# SI1125HD_replacement.net
KiCad netlist of a schematic drawn in Altium Designer
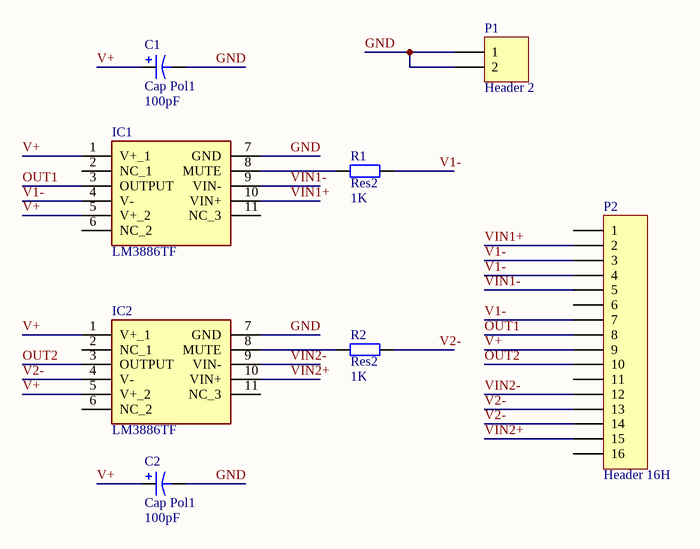
[diagram p0: SI1125HD_replacement.SchDoc]

(export (version "E")
  (design (tool "Eeschema 10.0.6"))
  (components
    (comp (ref "C1")
      (value "Cap Pol1")
      (footprint "RB5-10.5")
      (description "Polarized Capacitor (Radial)")
      (fields (field (name "ALTIUM_VALUE") "100pF") (field (name "PUBLISHER") "Altium Limited"))
      (libsource (lib "Miscellaneous Devices") (part "Cap Pol1"))
    )
    (comp (ref "C2")
      (value "Cap Pol1")
      (footprint "RB5-10.5")
      (description "Polarized Capacitor (Radial)")
      (fields (field (name "ALTIUM_VALUE") "100pF") (field (name "PUBLISHER") "Altium Limited"))
      (libsource (lib "Miscellaneous Devices") (part "Cap Pol1"))
    )
    (comp (ref "IC1")
      (value "LM3886TF")
      (footprint "SamacSys:TO158P462X2002X2328-11P")
      (description "Integrated Circuit")
      (fields (field (name "MOUSER PART NUMBER") "926-LM3886TF"))
      (libsource (lib "*") (part "LM3886TF"))
    )
    (comp (ref "IC2")
      (value "LM3886TF")
      (footprint "SamacSys:TO158P462X2002X2328-11P")
      (description "Integrated Circuit")
      (fields (field (name "MOUSER PART NUMBER") "926-LM3886TF"))
      (libsource (lib "*") (part "LM3886TF"))
    )
    (comp (ref "P1")
      (value "Header 2")
      (footprint "HDR1X2")
      (description "Header, 2-Pin")
      (fields (field (name "PUBLISHER") "Altium Limited"))
      (libsource (lib "Miscellaneous Connectors") (part "Header 2"))
    )
    (comp (ref "P2")
      (value "Header 16H")
      (footprint "HDR1X16H")
      (description "Header, 16-Pin, Right Angle")
      (fields (field (name "PUBLISHER") "Altium Limited"))
      (libsource (lib "Miscellaneous Connectors") (part "Header 16H"))
    )
    (comp (ref "R1")
      (value "Res2")
      (footprint "AXIAL-0.4")
      (description "Resistor")
      (fields (field (name "ALTIUM_VALUE") "1K") (field (name "PUBLISHER") "Altium Limited"))
      (libsource (lib "Miscellaneous Devices") (part "Res2"))
    )
    (comp (ref "R2")
      (value "Res2")
      (footprint "AXIAL-0.4")
      (description "Resistor")
      (fields (field (name "ALTIUM_VALUE") "1K") (field (name "PUBLISHER") "Altium Limited"))
      (libsource (lib "Miscellaneous Devices") (part "Res2"))
    )
  )
  (nets
    (net (code "1") (name "/GND") (class "Default")
      (node (ref "C1") (pin "2") (pinfunction "2_2") (pintype "passive"))
      (node (ref "C2") (pin "2") (pinfunction "2_2") (pintype "passive"))
      (node (ref "IC1") (pin "7") (pinfunction "GND_7") (pintype "passive"))
      (node (ref "IC2") (pin "7") (pinfunction "GND_7") (pintype "passive"))
      (node (ref "P1") (pin "1") (pinfunction "1_1") (pintype "passive"))
      (node (ref "P1") (pin "2") (pinfunction "2_2") (pintype "passive"))
    )
    (net (code "2") (name "/OUT1") (class "Default")
      (node (ref "IC1") (pin "3") (pinfunction "OUTPUT_3") (pintype "passive"))
      (node (ref "P2") (pin "8") (pinfunction "8_8") (pintype "passive"))
    )
    (net (code "3") (name "/OUT2") (class "Default")
      (node (ref "IC2") (pin "3") (pinfunction "OUTPUT_3") (pintype "passive"))
      (node (ref "P2") (pin "10") (pinfunction "10_10") (pintype "passive"))
    )
    (net (code "4") (name "/V+") (class "Default")
      (node (ref "C1") (pin "1") (pinfunction "1_1") (pintype "passive"))
      (node (ref "C2") (pin "1") (pinfunction "1_1") (pintype "passive"))
      (node (ref "IC1") (pin "1") (pinfunction "V+_1_1") (pintype "passive"))
      (node (ref "IC1") (pin "5") (pinfunction "V+_2_5") (pintype "passive"))
      (node (ref "IC2") (pin "1") (pinfunction "V+_1_1") (pintype "passive"))
      (node (ref "IC2") (pin "5") (pinfunction "V+_2_5") (pintype "passive"))
      (node (ref "P2") (pin "9") (pinfunction "9_9") (pintype "passive"))
    )
    (net (code "5") (name "/V1-") (class "Default")
      (node (ref "IC1") (pin "4") (pinfunction "V-_4") (pintype "passive"))
      (node (ref "P2") (pin "3") (pinfunction "3_3") (pintype "passive"))
      (node (ref "P2") (pin "4") (pinfunction "4_4") (pintype "passive"))
      (node (ref "P2") (pin "7") (pinfunction "7_7") (pintype "passive"))
      (node (ref "R1") (pin "2") (pinfunction "2_2") (pintype "passive"))
    )
    (net (code "6") (name "/V2-") (class "Default")
      (node (ref "IC2") (pin "4") (pinfunction "V-_4") (pintype "passive"))
      (node (ref "P2") (pin "13") (pinfunction "13_13") (pintype "passive"))
      (node (ref "P2") (pin "14") (pinfunction "14_14") (pintype "passive"))
      (node (ref "R2") (pin "2") (pinfunction "2_2") (pintype "passive"))
    )
    (net (code "7") (name "/VIN1+") (class "Default")
      (node (ref "IC1") (pin "10") (pinfunction "VIN+_10") (pintype "passive"))
      (node (ref "P2") (pin "2") (pinfunction "2_2") (pintype "passive"))
    )
    (net (code "8") (name "/VIN1-") (class "Default")
      (node (ref "IC1") (pin "9") (pinfunction "VIN-_9") (pintype "passive"))
      (node (ref "P2") (pin "5") (pinfunction "5_5") (pintype "passive"))
    )
    (net (code "9") (name "/VIN2+") (class "Default")
      (node (ref "IC2") (pin "10") (pinfunction "VIN+_10") (pintype "passive"))
      (node (ref "P2") (pin "15") (pinfunction "15_15") (pintype "passive"))
    )
    (net (code "10") (name "/VIN2-") (class "Default")
      (node (ref "IC2") (pin "9") (pinfunction "VIN-_9") (pintype "passive"))
      (node (ref "P2") (pin "12") (pinfunction "12_12") (pintype "passive"))
    )
    (net (code "11") (name "Net-(IC1-MUTE)") (class "Default")
      (node (ref "IC1") (pin "8") (pinfunction "MUTE_8") (pintype "passive"))
      (node (ref "R1") (pin "1") (pinfunction "1_1") (pintype "passive"))
    )
    (net (code "12") (name "Net-(IC2-MUTE)") (class "Default")
      (node (ref "IC2") (pin "8") (pinfunction "MUTE_8") (pintype "passive"))
      (node (ref "R2") (pin "1") (pinfunction "1_1") (pintype "passive"))
    )
    (net (code "13") (name "unconnected-(IC1-NC_1-Pad2)") (class "Default")
      (node (ref "IC1") (pin "2") (pinfunction "NC_1_2") (pintype "passive"))
    )
    (net (code "14") (name "unconnected-(IC1-NC_2-Pad6)") (class "Default")
      (node (ref "IC1") (pin "6") (pinfunction "NC_2_6") (pintype "passive"))
    )
    (net (code "15") (name "unconnected-(IC1-NC_3-Pad11)") (class "Default")
      (node (ref "IC1") (pin "11") (pinfunction "NC_3_11") (pintype "passive"))
    )
    (net (code "16") (name "unconnected-(IC2-NC_1-Pad2)") (class "Default")
      (node (ref "IC2") (pin "2") (pinfunction "NC_1_2") (pintype "passive"))
    )
    (net (code "17") (name "unconnected-(IC2-NC_2-Pad6)") (class "Default")
      (node (ref "IC2") (pin "6") (pinfunction "NC_2_6") (pintype "passive"))
    )
    (net (code "18") (name "unconnected-(IC2-NC_3-Pad11)") (class "Default")
      (node (ref "IC2") (pin "11") (pinfunction "NC_3_11") (pintype "passive"))
    )
    (net (code "19") (name "unconnected-(P2-Pad1)") (class "Default")
      (node (ref "P2") (pin "1") (pinfunction "1_1") (pintype "passive"))
    )
    (net (code "20") (name "unconnected-(P2-Pad6)") (class "Default")
      (node (ref "P2") (pin "6") (pinfunction "6_6") (pintype "passive"))
    )
    (net (code "21") (name "unconnected-(P2-Pad11)") (class "Default")
      (node (ref "P2") (pin "11") (pinfunction "11_11") (pintype "passive"))
    )
    (net (code "22") (name "unconnected-(P2-Pad16)") (class "Default")
      (node (ref "P2") (pin "16") (pinfunction "16_16") (pintype "passive"))
    )
  )
)
